# PCB1.net
KiCad netlist of a schematic drawn in EAGLE
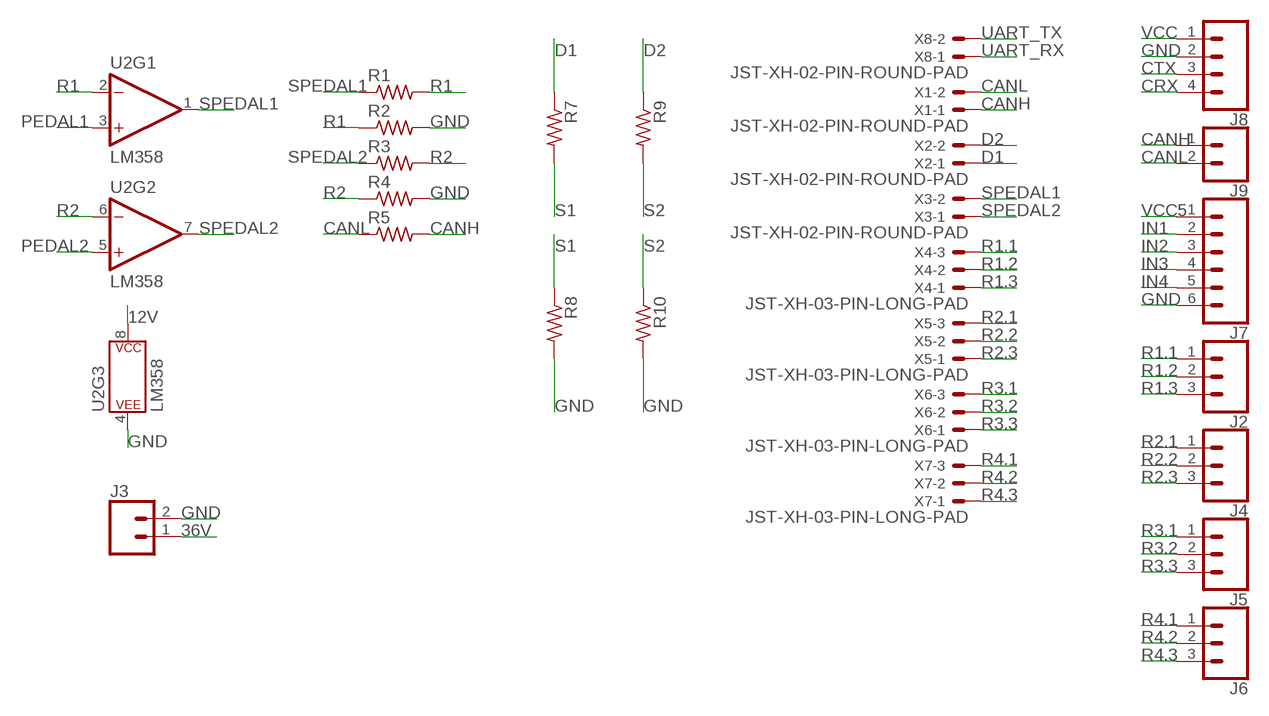
[diagram p0: schematic, sheet 1]
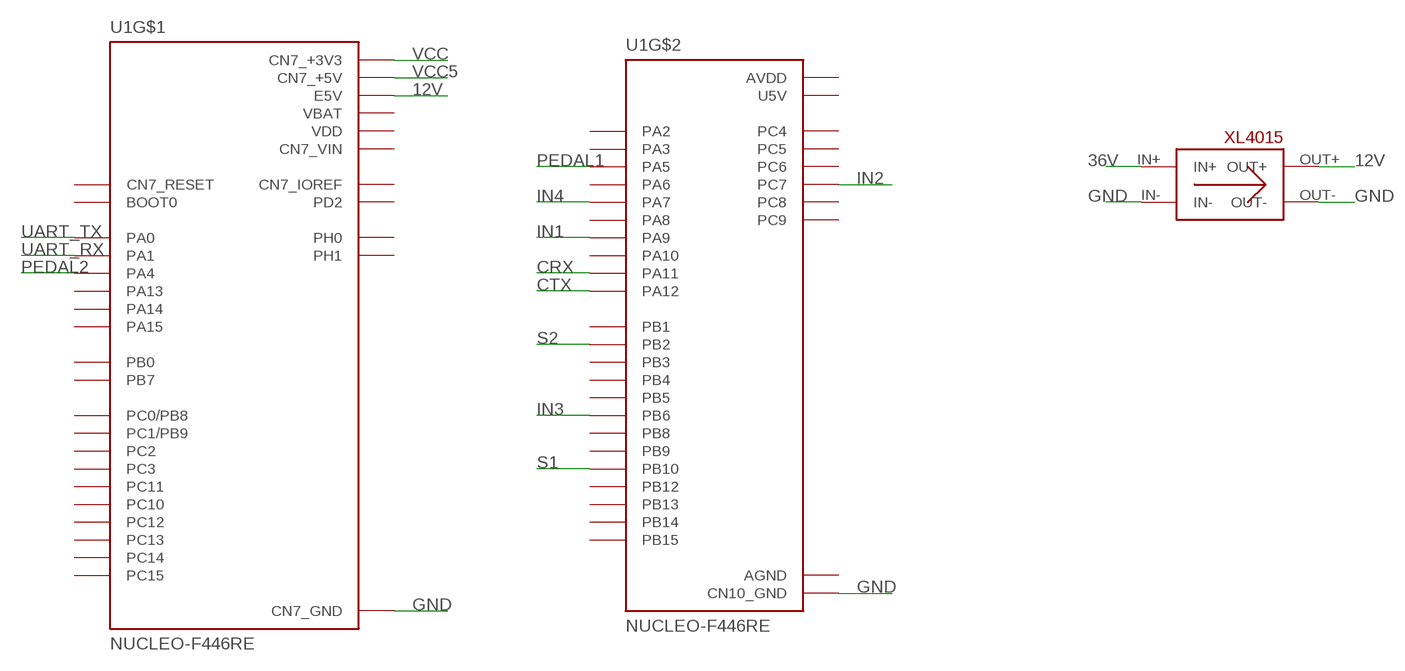
[diagram p1: schematic, sheet 2]

(export (version "E")
  (design (tool "Eeschema 10.0.6"))
  (components
    (comp (ref "J2")
      (value "CONN_03")
      (footprint "eagle-import:1X03")
      (libsource (lib "eagle-import") (part "CONN_03"))
    )
    (comp (ref "J3")
      (value "CONN_025MM")
      (footprint "eagle-import:SCREWTERMINAL-5MM-2")
      (libsource (lib "eagle-import") (part "CONN_025MM"))
    )
    (comp (ref "J4")
      (value "CONN_03")
      (footprint "eagle-import:1X03")
      (libsource (lib "eagle-import") (part "CONN_03"))
    )
    (comp (ref "J5")
      (value "CONN_03")
      (footprint "eagle-import:1X03")
      (libsource (lib "eagle-import") (part "CONN_03"))
    )
    (comp (ref "J6")
      (value "CONN_03")
      (footprint "eagle-import:1X03")
      (libsource (lib "eagle-import") (part "CONN_03"))
    )
    (comp (ref "J7")
      (value "CONN_06SILK_FEMALE_PTH")
      (footprint "eagle-import:1X06")
      (libsource (lib "eagle-import") (part "CONN_06SILK_FEMALE_PTH"))
    )
    (comp (ref "J8")
      (value "CONN_04")
      (footprint "eagle-import:1X04")
      (libsource (lib "eagle-import") (part "CONN_04"))
    )
    (comp (ref "J9")
      (value "CONN_02")
      (footprint "eagle-import:1X02")
      (libsource (lib "eagle-import") (part "CONN_02"))
    )
    (comp (ref "R1")
      (value "R-US_0207/10")
      (footprint "eagle-import:0207_10")
      (libsource (lib "eagle-import") (part "R-US_0207/10"))
    )
    (comp (ref "R2")
      (value "R-US_0207/10")
      (footprint "eagle-import:0207_10")
      (libsource (lib "eagle-import") (part "R-US_0207/10"))
    )
    (comp (ref "R3")
      (value "R-US_0207/10")
      (footprint "eagle-import:0207_10")
      (libsource (lib "eagle-import") (part "R-US_0207/10"))
    )
    (comp (ref "R4")
      (value "R-US_0207/10")
      (footprint "eagle-import:0207_10")
      (libsource (lib "eagle-import") (part "R-US_0207/10"))
    )
    (comp (ref "R5")
      (value "R-US_0207/10")
      (footprint "eagle-import:0207_10")
      (libsource (lib "eagle-import") (part "R-US_0207/10"))
    )
    (comp (ref "R7")
      (value "R-US_0207/10")
      (footprint "eagle-import:0207_10")
      (libsource (lib "eagle-import") (part "R-US_0207/10"))
    )
    (comp (ref "R8")
      (value "R-US_0207/10")
      (footprint "eagle-import:0207_10")
      (libsource (lib "eagle-import") (part "R-US_0207/10"))
    )
    (comp (ref "R9")
      (value "R-US_0207/10")
      (footprint "eagle-import:0207_10")
      (libsource (lib "eagle-import") (part "R-US_0207/10"))
    )
    (comp (ref "R10")
      (value "R-US_0207/10")
      (footprint "eagle-import:0207_10")
      (libsource (lib "eagle-import") (part "R-US_0207/10"))
    )
    (comp (ref "U2")
      (value "LM358")
      (footprint "eagle-import:DIP08")
      (libsource (lib "eagle-import") (part "LM358"))
    )
    (comp (ref "X1")
      (value "JST-XH-02-PIN-ROUND-PAD")
      (footprint "eagle-import:JST-XH-02-PACKAGE-ROUND-PAD")
      (libsource (lib "eagle-import") (part "JST-XH-02-PIN-ROUND-PAD"))
    )
    (comp (ref "X2")
      (value "JST-XH-02-PIN-ROUND-PAD")
      (footprint "eagle-import:JST-XH-02-PACKAGE-ROUND-PAD")
      (libsource (lib "eagle-import") (part "JST-XH-02-PIN-ROUND-PAD"))
    )
    (comp (ref "X3")
      (value "JST-XH-02-PIN-ROUND-PAD")
      (footprint "eagle-import:JST-XH-02-PACKAGE-ROUND-PAD")
      (libsource (lib "eagle-import") (part "JST-XH-02-PIN-ROUND-PAD"))
    )
    (comp (ref "X4")
      (value "JST-XH-03-PIN-LONG-PAD")
      (footprint "eagle-import:JST-XH-03-PACKAGE-LONG-PAD")
      (libsource (lib "eagle-import") (part "JST-XH-03-PIN-LONG-PAD"))
    )
    (comp (ref "X5")
      (value "JST-XH-03-PIN-LONG-PAD")
      (footprint "eagle-import:JST-XH-03-PACKAGE-LONG-PAD")
      (libsource (lib "eagle-import") (part "JST-XH-03-PIN-LONG-PAD"))
    )
    (comp (ref "X6")
      (value "JST-XH-03-PIN-LONG-PAD")
      (footprint "eagle-import:JST-XH-03-PACKAGE-LONG-PAD")
      (libsource (lib "eagle-import") (part "JST-XH-03-PIN-LONG-PAD"))
    )
    (comp (ref "X7")
      (value "JST-XH-03-PIN-LONG-PAD")
      (footprint "eagle-import:JST-XH-03-PACKAGE-LONG-PAD")
      (libsource (lib "eagle-import") (part "JST-XH-03-PIN-LONG-PAD"))
    )
    (comp (ref "X8")
      (value "JST-XH-02-PIN-ROUND-PAD")
      (footprint "eagle-import:JST-XH-02-PACKAGE-ROUND-PAD")
      (libsource (lib "eagle-import") (part "JST-XH-02-PIN-ROUND-PAD"))
    )
    (comp (ref "U$4")
      (value "XL4015")
      (footprint "eagle-import:XL4015")
      (libsource (lib "eagle-import") (part "XL4015"))
    )
    (comp (ref "U1")
      (value "NUCLEO-F446RE")
      (footprint "eagle-import:MODULE_NUCLEO-F446RE")
      (fields (field (name "MF") "STMicroelectronics"))
      (libsource (lib "eagle-import") (part "NUCLEO-F446RE"))
    )
  )
  (nets
    (net (code "1") (name "12V") (class "Default")
      (node (ref "U$4") (pin "OUT+") (pinfunction "OUT+_OUT+") (pintype "bidirectional"))
      (node (ref "U1") (pin "CN7_6") (pinfunction "E5V_CN7_6") (pintype "power_in"))
      (node (ref "U2") (pin "8") (pinfunction "P$V+_8") (pintype "bidirectional"))
    )
    (net (code "2") (name "36V") (class "Default")
      (node (ref "J3") (pin "1") (pinfunction "1_1") (pintype "passive"))
      (node (ref "U$4") (pin "IN+") (pinfunction "IN+_IN+") (pintype "bidirectional"))
    )
    (net (code "3") (name "AGND") (class "Default")
      (node (ref "U1") (pin "CN10_32") (pinfunction "AGND_CN10_32") (pintype "power_in"))
    )
    (net (code "4") (name "AVDD") (class "Default")
      (node (ref "U1") (pin "CN10_7") (pinfunction "AVDD_CN10_7") (pintype "power_in"))
    )
    (net (code "5") (name "CANH") (class "Default")
      (node (ref "J9") (pin "1") (pinfunction "1_1") (pintype "passive"))
      (node (ref "R5") (pin "2") (pinfunction "2_2") (pintype "passive"))
      (node (ref "X1") (pin "1") (pinfunction "S_1") (pintype "passive"))
    )
    (net (code "6") (name "CANL") (class "Default")
      (node (ref "J9") (pin "2") (pinfunction "2_2") (pintype "passive"))
      (node (ref "R5") (pin "1") (pinfunction "1_1") (pintype "passive"))
      (node (ref "X1") (pin "2") (pinfunction "S_2") (pintype "passive"))
    )
    (net (code "7") (name "CN7_VIN") (class "Default")
      (node (ref "U1") (pin "CN7_24") (pinfunction "CN7_VIN_CN7_24") (pintype "power_in"))
    )
    (net (code "8") (name "CRX") (class "Default")
      (node (ref "J8") (pin "4") (pinfunction "4_4") (pintype "passive"))
      (node (ref "U1") (pin "CN10_14") (pinfunction "PA11_CN10_14") (pintype "bidirectional"))
    )
    (net (code "9") (name "CTX") (class "Default")
      (node (ref "J8") (pin "3") (pinfunction "3_3") (pintype "passive"))
      (node (ref "U1") (pin "CN10_12") (pinfunction "PA12_CN10_12") (pintype "bidirectional"))
    )
    (net (code "10") (name "D1") (class "Default")
      (node (ref "R7") (pin "1") (pinfunction "1_1") (pintype "passive"))
      (node (ref "X2") (pin "1") (pinfunction "S_1") (pintype "passive"))
    )
    (net (code "11") (name "D2") (class "Default")
      (node (ref "R9") (pin "1") (pinfunction "1_1") (pintype "passive"))
      (node (ref "X2") (pin "2") (pinfunction "S_2") (pintype "passive"))
    )
    (net (code "12") (name "GND") (class "Default")
      (node (ref "J3") (pin "2") (pinfunction "2_2") (pintype "passive"))
      (node (ref "J7") (pin "6") (pinfunction "6_6") (pintype "passive"))
      (node (ref "J8") (pin "2") (pinfunction "2_2") (pintype "passive"))
      (node (ref "R10") (pin "2") (pinfunction "2_2") (pintype "passive"))
      (node (ref "R2") (pin "2") (pinfunction "2_2") (pintype "passive"))
      (node (ref "R4") (pin "2") (pinfunction "2_2") (pintype "passive"))
      (node (ref "R8") (pin "2") (pinfunction "2_2") (pintype "passive"))
      (node (ref "U$4") (pin "IN-") (pinfunction "IN-_IN-") (pintype "bidirectional"))
      (node (ref "U$4") (pin "OUT-") (pinfunction "OUT-_OUT-") (pintype "bidirectional"))
      (node (ref "U1") (pin "CN10_20") (pinfunction "CN10_GND_CN10_20") (pintype "power_in"))
      (node (ref "U1") (pin "CN10_9") (pinfunction "CN10_GND_CN10_9") (pintype "power_in"))
      (node (ref "U1") (pin "CN7_19") (pinfunction "CN7_GND_CN7_19") (pintype "power_in"))
      (node (ref "U1") (pin "CN7_20") (pinfunction "CN7_GND_CN7_20") (pintype "power_in"))
      (node (ref "U1") (pin "CN7_22") (pinfunction "CN7_GND_CN7_22") (pintype "power_in"))
      (node (ref "U1") (pin "CN7_8") (pinfunction "CN7_GND_CN7_8") (pintype "power_in"))
      (node (ref "U2") (pin "4") (pinfunction "P$V-_4") (pintype "bidirectional"))
    )
    (net (code "13") (name "IN1") (class "Default")
      (node (ref "J7") (pin "2") (pinfunction "2_2") (pintype "passive"))
      (node (ref "U1") (pin "CN10_21") (pinfunction "PA9_CN10_21") (pintype "bidirectional"))
    )
    (net (code "14") (name "IN2") (class "Default")
      (node (ref "J7") (pin "3") (pinfunction "3_3") (pintype "passive"))
      (node (ref "U1") (pin "CN10_19") (pinfunction "PC7_CN10_19") (pintype "bidirectional"))
    )
    (net (code "15") (name "IN3") (class "Default")
      (node (ref "J7") (pin "4") (pinfunction "4_4") (pintype "passive"))
      (node (ref "U1") (pin "CN10_17") (pinfunction "PB6_CN10_17") (pintype "bidirectional"))
    )
    (net (code "16") (name "IN4") (class "Default")
      (node (ref "J7") (pin "5") (pinfunction "5_5") (pintype "passive"))
      (node (ref "U1") (pin "CN10_15") (pinfunction "PA7_CN10_15") (pintype "bidirectional"))
    )
    (net (code "17") (name "PEDAL1") (class "Default")
      (node (ref "U1") (pin "CN10_11") (pinfunction "PA5_CN10_11") (pintype "bidirectional"))
      (node (ref "U2") (pin "3") (pinfunction "+IN_3") (pintype "input"))
    )
    (net (code "18") (name "PEDAL2") (class "Default")
      (node (ref "U1") (pin "CN7_32") (pinfunction "PA4_CN7_32") (pintype "bidirectional"))
      (node (ref "U2") (pin "5") (pinfunction "+IN_5") (pintype "input"))
    )
    (net (code "19") (name "R1") (class "Default")
      (node (ref "R1") (pin "2") (pinfunction "2_2") (pintype "passive"))
      (node (ref "R2") (pin "1") (pinfunction "1_1") (pintype "passive"))
      (node (ref "U2") (pin "2") (pinfunction "-IN_2") (pintype "input"))
    )
    (net (code "20") (name "R1.1") (class "Default")
      (node (ref "J2") (pin "1") (pinfunction "1_1") (pintype "passive"))
      (node (ref "X4") (pin "3") (pinfunction "S_3") (pintype "passive"))
    )
    (net (code "21") (name "R1.2") (class "Default")
      (node (ref "J2") (pin "2") (pinfunction "2_2") (pintype "passive"))
      (node (ref "X4") (pin "2") (pinfunction "S_2") (pintype "passive"))
    )
    (net (code "22") (name "R1.3") (class "Default")
      (node (ref "J2") (pin "3") (pinfunction "3_3") (pintype "passive"))
      (node (ref "X4") (pin "1") (pinfunction "S_1") (pintype "passive"))
    )
    (net (code "23") (name "R2") (class "Default")
      (node (ref "R3") (pin "2") (pinfunction "2_2") (pintype "passive"))
      (node (ref "R4") (pin "1") (pinfunction "1_1") (pintype "passive"))
      (node (ref "U2") (pin "6") (pinfunction "-IN_6") (pintype "input"))
    )
    (net (code "24") (name "R2.1") (class "Default")
      (node (ref "J4") (pin "1") (pinfunction "1_1") (pintype "passive"))
      (node (ref "X5") (pin "3") (pinfunction "S_3") (pintype "passive"))
    )
    (net (code "25") (name "R2.2") (class "Default")
      (node (ref "J4") (pin "2") (pinfunction "2_2") (pintype "passive"))
      (node (ref "X5") (pin "2") (pinfunction "S_2") (pintype "passive"))
    )
    (net (code "26") (name "R2.3") (class "Default")
      (node (ref "J4") (pin "3") (pinfunction "3_3") (pintype "passive"))
      (node (ref "X5") (pin "1") (pinfunction "S_1") (pintype "passive"))
    )
    (net (code "27") (name "R3.1") (class "Default")
      (node (ref "J5") (pin "1") (pinfunction "1_1") (pintype "passive"))
      (node (ref "X6") (pin "3") (pinfunction "S_3") (pintype "passive"))
    )
    (net (code "28") (name "R3.2") (class "Default")
      (node (ref "J5") (pin "2") (pinfunction "2_2") (pintype "passive"))
      (node (ref "X6") (pin "2") (pinfunction "S_2") (pintype "passive"))
    )
    (net (code "29") (name "R3.3") (class "Default")
      (node (ref "J5") (pin "3") (pinfunction "3_3") (pintype "passive"))
      (node (ref "X6") (pin "1") (pinfunction "S_1") (pintype "passive"))
    )
    (net (code "30") (name "R4.1") (class "Default")
      (node (ref "J6") (pin "1") (pinfunction "1_1") (pintype "passive"))
      (node (ref "X7") (pin "3") (pinfunction "S_3") (pintype "passive"))
    )
    (net (code "31") (name "R4.2") (class "Default")
      (node (ref "J6") (pin "2") (pinfunction "2_2") (pintype "passive"))
      (node (ref "X7") (pin "2") (pinfunction "S_2") (pintype "passive"))
    )
    (net (code "32") (name "R4.3") (class "Default")
      (node (ref "J6") (pin "3") (pinfunction "3_3") (pintype "passive"))
      (node (ref "X7") (pin "1") (pinfunction "S_1") (pintype "passive"))
    )
    (net (code "33") (name "S1") (class "Default")
      (node (ref "R7") (pin "2") (pinfunction "2_2") (pintype "passive"))
      (node (ref "R8") (pin "1") (pinfunction "1_1") (pintype "passive"))
      (node (ref "U1") (pin "CN10_25") (pinfunction "PB10_CN10_25") (pintype "bidirectional"))
    )
    (net (code "34") (name "S2") (class "Default")
      (node (ref "R10") (pin "1") (pinfunction "1_1") (pintype "passive"))
      (node (ref "R9") (pin "2") (pinfunction "2_2") (pintype "passive"))
      (node (ref "U1") (pin "CN10_22") (pinfunction "PB2_CN10_22") (pintype "bidirectional"))
    )
    (net (code "35") (name "SPEDAL1") (class "Default")
      (node (ref "R1") (pin "1") (pinfunction "1_1") (pintype "passive"))
      (node (ref "U2") (pin "1") (pinfunction "OUT_1") (pintype "output"))
      (node (ref "X3") (pin "2") (pinfunction "S_2") (pintype "passive"))
    )
    (net (code "36") (name "SPEDAL2") (class "Default")
      (node (ref "R3") (pin "1") (pinfunction "1_1") (pintype "passive"))
      (node (ref "U2") (pin "7") (pinfunction "OUT_7") (pintype "output"))
      (node (ref "X3") (pin "1") (pinfunction "S_1") (pintype "passive"))
    )
    (net (code "37") (name "U5V") (class "Default")
      (node (ref "U1") (pin "CN10_8") (pinfunction "U5V_CN10_8") (pintype "power_in"))
    )
    (net (code "38") (name "UART_RX") (class "Default")
      (node (ref "U1") (pin "CN7_30") (pinfunction "PA1_CN7_30") (pintype "bidirectional"))
      (node (ref "X8") (pin "1") (pinfunction "S_1") (pintype "passive"))
    )
    (net (code "39") (name "UART_TX") (class "Default")
      (node (ref "U1") (pin "CN7_28") (pinfunction "PA0_CN7_28") (pintype "bidirectional"))
      (node (ref "X8") (pin "2") (pinfunction "S_2") (pintype "passive"))
    )
    (net (code "40") (name "VBAT") (class "Default")
      (node (ref "U1") (pin "CN7_33") (pinfunction "VBAT_CN7_33") (pintype "power_in"))
    )
    (net (code "41") (name "VCC") (class "Default")
      (node (ref "J8") (pin "1") (pinfunction "1_1") (pintype "passive"))
      (node (ref "U1") (pin "CN7_16") (pinfunction "CN7_+3V3_CN7_16") (pintype "power_in"))
    )
    (net (code "42") (name "VCC5") (class "Default")
      (node (ref "J7") (pin "1") (pinfunction "1_1") (pintype "passive"))
      (node (ref "U1") (pin "CN7_18") (pinfunction "CN7_+5V_CN7_18") (pintype "power_in"))
    )
    (net (code "43") (name "VDD") (class "Default")
      (node (ref "U1") (pin "CN7_5") (pinfunction "VDD_CN7_5") (pintype "power_in"))
    )
    (net (code "44") (name "unconnected-(U1A-BOOT0-PadCN7_7)") (class "Default")
      (node (ref "U1") (pin "CN7_7") (pinfunction "BOOT0_CN7_7") (pintype "bidirectional"))
    )
    (net (code "45") (name "unconnected-(U1A-CN7_IOREF-PadCN7_12)") (class "Default")
      (node (ref "U1") (pin "CN7_12") (pinfunction "CN7_IOREF_CN7_12") (pintype "bidirectional"))
    )
    (net (code "46") (name "unconnected-(U1A-CN7_RESET-PadCN7_14)") (class "Default")
      (node (ref "U1") (pin "CN7_14") (pinfunction "CN7_RESET_CN7_14") (pintype "bidirectional"))
    )
    (net (code "47") (name "unconnected-(U1A-PA13-PadCN7_13)") (class "Default")
      (node (ref "U1") (pin "CN7_13") (pinfunction "PA13_CN7_13") (pintype "bidirectional"))
    )
    (net (code "48") (name "unconnected-(U1A-PA14-PadCN7_15)") (class "Default")
      (node (ref "U1") (pin "CN7_15") (pinfunction "PA14_CN7_15") (pintype "bidirectional"))
    )
    (net (code "49") (name "unconnected-(U1A-PA15-PadCN7_17)") (class "Default")
      (node (ref "U1") (pin "CN7_17") (pinfunction "PA15_CN7_17") (pintype "bidirectional"))
    )
    (net (code "50") (name "unconnected-(U1A-PB0-PadCN7_34)") (class "Default")
      (node (ref "U1") (pin "CN7_34") (pinfunction "PB0_CN7_34") (pintype "bidirectional"))
    )
    (net (code "51") (name "unconnected-(U1A-PB7-PadCN7_21)") (class "Default")
      (node (ref "U1") (pin "CN7_21") (pinfunction "PB7_CN7_21") (pintype "bidirectional"))
    )
    (net (code "52") (name "unconnected-(U1A-PC0{slash}PB8-PadCN7_38)") (class "Default")
      (node (ref "U1") (pin "CN7_38") (pinfunction "PC0/PB8_CN7_38") (pintype "bidirectional"))
    )
    (net (code "53") (name "unconnected-(U1A-PC1{slash}PB9-PadCN7_36)") (class "Default")
      (node (ref "U1") (pin "CN7_36") (pinfunction "PC1/PB9_CN7_36") (pintype "bidirectional"))
    )
    (net (code "54") (name "unconnected-(U1A-PC2-PadCN7_35)") (class "Default")
      (node (ref "U1") (pin "CN7_35") (pinfunction "PC2_CN7_35") (pintype "bidirectional"))
    )
    (net (code "55") (name "unconnected-(U1A-PC3-PadCN7_37)") (class "Default")
      (node (ref "U1") (pin "CN7_37") (pinfunction "PC3_CN7_37") (pintype "bidirectional"))
    )
    (net (code "56") (name "unconnected-(U1A-PC10-PadCN7_1)") (class "Default")
      (node (ref "U1") (pin "CN7_1") (pinfunction "PC10_CN7_1") (pintype "bidirectional"))
    )
    (net (code "57") (name "unconnected-(U1A-PC11-PadCN7_2)") (class "Default")
      (node (ref "U1") (pin "CN7_2") (pinfunction "PC11_CN7_2") (pintype "bidirectional"))
    )
    (net (code "58") (name "unconnected-(U1A-PC12-PadCN7_3)") (class "Default")
      (node (ref "U1") (pin "CN7_3") (pinfunction "PC12_CN7_3") (pintype "bidirectional"))
    )
    (net (code "59") (name "unconnected-(U1A-PC13-PadCN7_23)") (class "Default")
      (node (ref "U1") (pin "CN7_23") (pinfunction "PC13_CN7_23") (pintype "bidirectional"))
    )
    (net (code "60") (name "unconnected-(U1A-PC14-PadCN7_25)") (class "Default")
      (node (ref "U1") (pin "CN7_25") (pinfunction "PC14_CN7_25") (pintype "bidirectional"))
    )
    (net (code "61") (name "unconnected-(U1A-PC15-PadCN7_27)") (class "Default")
      (node (ref "U1") (pin "CN7_27") (pinfunction "PC15_CN7_27") (pintype "bidirectional"))
    )
    (net (code "62") (name "unconnected-(U1A-PD2-PadCN7_4)") (class "Default")
      (node (ref "U1") (pin "CN7_4") (pinfunction "PD2_CN7_4") (pintype "bidirectional"))
    )
    (net (code "63") (name "unconnected-(U1A-PH0-PadCN7_29)") (class "Default")
      (node (ref "U1") (pin "CN7_29") (pinfunction "PH0_CN7_29") (pintype "bidirectional"))
    )
    (net (code "64") (name "unconnected-(U1A-PH1-PadCN7_31)") (class "Default")
      (node (ref "U1") (pin "CN7_31") (pinfunction "PH1_CN7_31") (pintype "bidirectional"))
    )
    (net (code "65") (name "unconnected-(U1B-PA2-PadCN10_35)") (class "Default")
      (node (ref "U1") (pin "CN10_35") (pinfunction "PA2_CN10_35") (pintype "bidirectional"))
    )
    (net (code "66") (name "unconnected-(U1B-PA3-PadCN10_37)") (class "Default")
      (node (ref "U1") (pin "CN10_37") (pinfunction "PA3_CN10_37") (pintype "bidirectional"))
    )
    (net (code "67") (name "unconnected-(U1B-PA6-PadCN10_13)") (class "Default")
      (node (ref "U1") (pin "CN10_13") (pinfunction "PA6_CN10_13") (pintype "bidirectional"))
    )
    (net (code "68") (name "unconnected-(U1B-PA8-PadCN10_23)") (class "Default")
      (node (ref "U1") (pin "CN10_23") (pinfunction "PA8_CN10_23") (pintype "bidirectional"))
    )
    (net (code "69") (name "unconnected-(U1B-PA10-PadCN10_33)") (class "Default")
      (node (ref "U1") (pin "CN10_33") (pinfunction "PA10_CN10_33") (pintype "bidirectional"))
    )
    (net (code "70") (name "unconnected-(U1B-PB1-PadCN10_24)") (class "Default")
      (node (ref "U1") (pin "CN10_24") (pinfunction "PB1_CN10_24") (pintype "bidirectional"))
    )
    (net (code "71") (name "unconnected-(U1B-PB3-PadCN10_31)") (class "Default")
      (node (ref "U1") (pin "CN10_31") (pinfunction "PB3_CN10_31") (pintype "bidirectional"))
    )
    (net (code "72") (name "unconnected-(U1B-PB4-PadCN10_27)") (class "Default")
      (node (ref "U1") (pin "CN10_27") (pinfunction "PB4_CN10_27") (pintype "bidirectional"))
    )
    (net (code "73") (name "unconnected-(U1B-PB5-PadCN10_29)") (class "Default")
      (node (ref "U1") (pin "CN10_29") (pinfunction "PB5_CN10_29") (pintype "bidirectional"))
    )
    (net (code "74") (name "unconnected-(U1B-PB8-PadCN10_3)") (class "Default")
      (node (ref "U1") (pin "CN10_3") (pinfunction "PB8_CN10_3") (pintype "bidirectional"))
    )
    (net (code "75") (name "unconnected-(U1B-PB9-PadCN10_5)") (class "Default")
      (node (ref "U1") (pin "CN10_5") (pinfunction "PB9_CN10_5") (pintype "bidirectional"))
    )
    (net (code "76") (name "unconnected-(U1B-PB12-PadCN10_16)") (class "Default")
      (node (ref "U1") (pin "CN10_16") (pinfunction "PB12_CN10_16") (pintype "bidirectional"))
    )
    (net (code "77") (name "unconnected-(U1B-PB13-PadCN10_30)") (class "Default")
      (node (ref "U1") (pin "CN10_30") (pinfunction "PB13_CN10_30") (pintype "bidirectional"))
    )
    (net (code "78") (name "unconnected-(U1B-PB14-PadCN10_28)") (class "Default")
      (node (ref "U1") (pin "CN10_28") (pinfunction "PB14_CN10_28") (pintype "bidirectional"))
    )
    (net (code "79") (name "unconnected-(U1B-PB15-PadCN10_26)") (class "Default")
      (node (ref "U1") (pin "CN10_26") (pinfunction "PB15_CN10_26") (pintype "bidirectional"))
    )
    (net (code "80") (name "unconnected-(U1B-PC4-PadCN10_34)") (class "Default")
      (node (ref "U1") (pin "CN10_34") (pinfunction "PC4_CN10_34") (pintype "bidirectional"))
    )
    (net (code "81") (name "unconnected-(U1B-PC5-PadCN10_6)") (class "Default")
      (node (ref "U1") (pin "CN10_6") (pinfunction "PC5_CN10_6") (pintype "bidirectional"))
    )
    (net (code "82") (name "unconnected-(U1B-PC6-PadCN10_4)") (class "Default")
      (node (ref "U1") (pin "CN10_4") (pinfunction "PC6_CN10_4") (pintype "bidirectional"))
    )
    (net (code "83") (name "unconnected-(U1B-PC8-PadCN10_2)") (class "Default")
      (node (ref "U1") (pin "CN10_2") (pinfunction "PC8_CN10_2") (pintype "bidirectional"))
    )
    (net (code "84") (name "unconnected-(U1B-PC9-PadCN10_1)") (class "Default")
      (node (ref "U1") (pin "CN10_1") (pinfunction "PC9_CN10_1") (pintype "bidirectional"))
    )
  )
)
